# ISEGYE_IDOL.net
KiCad netlist of a schematic drawn in Altium Designer
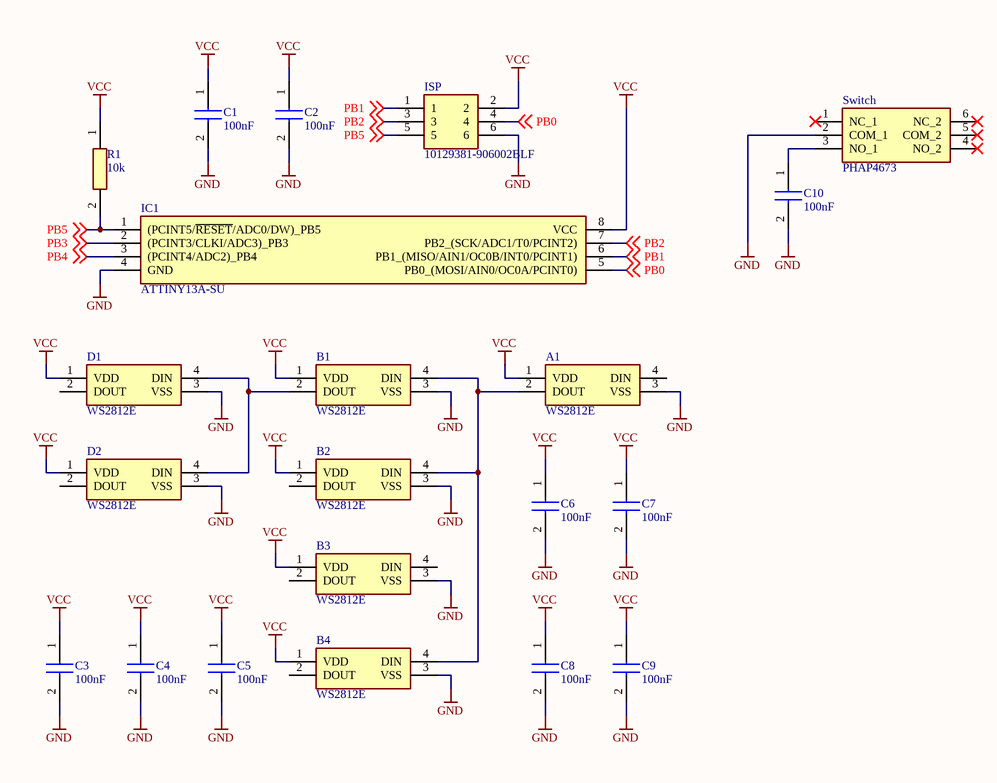
[diagram p0: ISEGYE_IDOL.SchDoc]

(export (version "E")
  (design (tool "Eeschema 10.0.6"))
  (components
    (comp (ref "A1")
      (value "WS2812E")
      (footprint "SamacSys:WS2812E")
      (description "LED")
      (libsource (lib "*") (part "WS2812E"))
    )
    (comp (ref "B1")
      (value "WS2812E")
      (footprint "SamacSys:WS2812E")
      (description "LED")
      (libsource (lib "*") (part "WS2812E"))
    )
    (comp (ref "B2")
      (value "WS2812E")
      (footprint "SamacSys:WS2812E")
      (description "LED")
      (libsource (lib "*") (part "WS2812E"))
    )
    (comp (ref "B3")
      (value "WS2812E")
      (footprint "SamacSys:WS2812E")
      (description "LED")
      (libsource (lib "*") (part "WS2812E"))
    )
    (comp (ref "B4")
      (value "WS2812E")
      (footprint "SamacSys:WS2812E")
      (description "LED")
      (libsource (lib "*") (part "WS2812E"))
    )
    (comp (ref "C1")
      (value "100nF")
      (footprint "SamacSys:CAPC2012X94N")
      (description "Capacitor")
      (fields
        (field (name "MANUFACTURER_PART_NUMBER") "08055A130JAT2A")
        (field (name "MOUSER PART NUMBER") "581-08055A130JAT2A")
      )
      (libsource (lib "*") (part "08055A130JAT2A"))
    )
    (comp (ref "C2")
      (value "100nF")
      (footprint "SamacSys:CAPC2012X94N")
      (description "Capacitor")
      (fields
        (field (name "MANUFACTURER_PART_NUMBER") "08055A130JAT2A")
        (field (name "MOUSER PART NUMBER") "581-08055A130JAT2A")
      )
      (libsource (lib "*") (part "08055A130JAT2A"))
    )
    (comp (ref "C3")
      (value "100nF")
      (footprint "SamacSys:CAPC2012X94N")
      (description "Capacitor")
      (fields
        (field (name "MANUFACTURER_PART_NUMBER") "08055A130JAT2A")
        (field (name "MOUSER PART NUMBER") "581-08055A130JAT2A")
      )
      (libsource (lib "*") (part "08055A130JAT2A"))
    )
    (comp (ref "C4")
      (value "100nF")
      (footprint "SamacSys:CAPC2012X94N")
      (description "Capacitor")
      (fields
        (field (name "MANUFACTURER_PART_NUMBER") "08055A130JAT2A")
        (field (name "MOUSER PART NUMBER") "581-08055A130JAT2A")
      )
      (libsource (lib "*") (part "08055A130JAT2A"))
    )
    (comp (ref "C5")
      (value "100nF")
      (footprint "SamacSys:CAPC2012X94N")
      (description "Capacitor")
      (fields
        (field (name "MANUFACTURER_PART_NUMBER") "08055A130JAT2A")
        (field (name "MOUSER PART NUMBER") "581-08055A130JAT2A")
      )
      (libsource (lib "*") (part "08055A130JAT2A"))
    )
    (comp (ref "C6")
      (value "100nF")
      (footprint "SamacSys:CAPC2012X94N")
      (description "Capacitor")
      (fields
        (field (name "MANUFACTURER_PART_NUMBER") "08055A130JAT2A")
        (field (name "MOUSER PART NUMBER") "581-08055A130JAT2A")
      )
      (libsource (lib "*") (part "08055A130JAT2A"))
    )
    (comp (ref "C7")
      (value "100nF")
      (footprint "SamacSys:CAPC2012X94N")
      (description "Capacitor")
      (fields
        (field (name "MANUFACTURER_PART_NUMBER") "08055A130JAT2A")
        (field (name "MOUSER PART NUMBER") "581-08055A130JAT2A")
      )
      (libsource (lib "*") (part "08055A130JAT2A"))
    )
    (comp (ref "C8")
      (value "100nF")
      (footprint "SamacSys:CAPC2012X94N")
      (description "Capacitor")
      (fields
        (field (name "MANUFACTURER_PART_NUMBER") "08055A130JAT2A")
        (field (name "MOUSER PART NUMBER") "581-08055A130JAT2A")
      )
      (libsource (lib "*") (part "08055A130JAT2A"))
    )
    (comp (ref "C9")
      (value "100nF")
      (footprint "SamacSys:CAPC2012X94N")
      (description "Capacitor")
      (fields
        (field (name "MANUFACTURER_PART_NUMBER") "08055A130JAT2A")
        (field (name "MOUSER PART NUMBER") "581-08055A130JAT2A")
      )
      (libsource (lib "*") (part "08055A130JAT2A"))
    )
    (comp (ref "C10")
      (value "100nF")
      (footprint "SamacSys:CAPC2012X94N")
      (description "Capacitor")
      (fields
        (field (name "MANUFACTURER_PART_NUMBER") "08055A130JAT2A")
        (field (name "MOUSER PART NUMBER") "581-08055A130JAT2A")
      )
      (libsource (lib "*") (part "08055A130JAT2A"))
    )
    (comp (ref "D1")
      (value "WS2812E")
      (footprint "SamacSys:WS2812E")
      (description "LED")
      (libsource (lib "*") (part "WS2812E"))
    )
    (comp (ref "D2")
      (value "WS2812E")
      (footprint "SamacSys:WS2812E")
      (description "LED")
      (libsource (lib "*") (part "WS2812E"))
    )
    (comp (ref "IC1")
      (value "ATTINY13A-SU")
      (footprint "SamacSys:SOIC127P798X216-8N")
      (description "Integrated Circuit")
      (fields (field (name "MOUSER PART NUMBER") "556-ATTINY13A-SU"))
      (libsource (lib "*") (part "ATTINY13A-SU"))
    )
    (comp (ref "ISP")
      (value "10129381-906002BLF")
      (footprint "SamacSys:HDRV6W67P254_2X3_762X483X858P")
      (description "Connector")
      (fields (field (name "MOUSER PART NUMBER") "649-1012938190602BLF"))
      (libsource (lib "*") (part "10129381-906002BLF"))
    )
    (comp (ref "R1")
      (value "10k")
      (footprint "SamacSys:RESC2012X65N")
      (description "Resistor")
      (fields (field (name "MANUFACTURER_PART_NUMBER") "NTR10B1002CTRF"))
      (libsource (lib "*") (part "NTR10B1002CTRF"))
    )
    (comp (ref "Switch")
      (value "PHAP4673")
      (footprint "SamacSys:PHAP4673")
      (description "Switch")
      (fields (field (name "MOUSER PART NUMBER") "642-PHAP4673"))
      (libsource (lib "*") (part "PHAP4673"))
    )
  )
  (nets
    (net (code "1") (name "GND") (class "Default")
      (node (ref "A1") (pin "3") (pinfunction "VSS_3") (pintype "passive"))
      (node (ref "B1") (pin "3") (pinfunction "VSS_3") (pintype "passive"))
      (node (ref "B2") (pin "3") (pinfunction "VSS_3") (pintype "passive"))
      (node (ref "B3") (pin "3") (pinfunction "VSS_3") (pintype "passive"))
      (node (ref "B4") (pin "3") (pinfunction "VSS_3") (pintype "passive"))
      (node (ref "C1") (pin "2") (pinfunction "2_2") (pintype "passive"))
      (node (ref "C10") (pin "2") (pinfunction "2_2") (pintype "passive"))
      (node (ref "C2") (pin "2") (pinfunction "2_2") (pintype "passive"))
      (node (ref "C3") (pin "2") (pinfunction "2_2") (pintype "passive"))
      (node (ref "C4") (pin "2") (pinfunction "2_2") (pintype "passive"))
      (node (ref "C5") (pin "2") (pinfunction "2_2") (pintype "passive"))
      (node (ref "C6") (pin "2") (pinfunction "2_2") (pintype "passive"))
      (node (ref "C7") (pin "2") (pinfunction "2_2") (pintype "passive"))
      (node (ref "C8") (pin "2") (pinfunction "2_2") (pintype "passive"))
      (node (ref "C9") (pin "2") (pinfunction "2_2") (pintype "passive"))
      (node (ref "D1") (pin "3") (pinfunction "VSS_3") (pintype "passive"))
      (node (ref "D2") (pin "3") (pinfunction "VSS_3") (pintype "passive"))
      (node (ref "IC1") (pin "4") (pinfunction "GND_4") (pintype "passive"))
      (node (ref "ISP") (pin "6") (pinfunction "6_6") (pintype "passive"))
      (node (ref "Switch") (pin "2") (pinfunction "COM_1_2") (pintype "passive"))
    )
    (net (code "2") (name "Net-(A1-DOUT)") (class "Default")
      (node (ref "A1") (pin "2") (pinfunction "DOUT_2") (pintype "passive"))
      (node (ref "B1") (pin "4") (pinfunction "DIN_4") (pintype "passive"))
      (node (ref "B2") (pin "4") (pinfunction "DIN_4") (pintype "passive"))
      (node (ref "B4") (pin "4") (pinfunction "DIN_4") (pintype "passive"))
    )
    (net (code "3") (name "Net-(B1-DOUT)") (class "Default")
      (node (ref "B1") (pin "2") (pinfunction "DOUT_2") (pintype "passive"))
      (node (ref "D1") (pin "4") (pinfunction "DIN_4") (pintype "passive"))
      (node (ref "D2") (pin "4") (pinfunction "DIN_4") (pintype "passive"))
    )
    (net (code "4") (name "Net-(Switch-NO_1)") (class "Default")
      (node (ref "C10") (pin "1") (pinfunction "1_1") (pintype "passive"))
      (node (ref "Switch") (pin "3") (pinfunction "NO_1_3") (pintype "passive"))
    )
    (net (code "5") (name "PB0") (class "Default")
      (node (ref "IC1") (pin "5") (pinfunction "PB0_(MOSI/AIN0/OC0A/PCINT0)_5") (pintype "passive"))
      (node (ref "ISP") (pin "4") (pinfunction "4_4") (pintype "passive"))
    )
    (net (code "6") (name "PB1") (class "Default")
      (node (ref "IC1") (pin "6") (pinfunction "PB1_(MISO/AIN1/OC0B/INT0/PCINT1)_6") (pintype "passive"))
      (node (ref "ISP") (pin "1") (pinfunction "1_1") (pintype "passive"))
    )
    (net (code "7") (name "PB2") (class "Default")
      (node (ref "IC1") (pin "7") (pinfunction "PB2_(SCK/ADC1/T0/PCINT2)_7") (pintype "passive"))
      (node (ref "ISP") (pin "3") (pinfunction "3_3") (pintype "passive"))
    )
    (net (code "8") (name "PB3") (class "Default")
      (node (ref "IC1") (pin "2") (pinfunction "(PCINT3/CLKI/ADC3)_PB3_2") (pintype "passive"))
    )
    (net (code "9") (name "PB4") (class "Default")
      (node (ref "IC1") (pin "3") (pinfunction "(PCINT4/ADC2)_PB4_3") (pintype "passive"))
    )
    (net (code "10") (name "PB5") (class "Default")
      (node (ref "IC1") (pin "1") (pinfunction "(PCINT5/~{RESET}/ADC0/DW)_PB5_1") (pintype "passive"))
      (node (ref "ISP") (pin "5") (pinfunction "5_5") (pintype "passive"))
      (node (ref "R1") (pin "2") (pinfunction "2_2") (pintype "passive"))
    )
    (net (code "11") (name "VCC") (class "Default")
      (node (ref "A1") (pin "1") (pinfunction "VDD_1") (pintype "passive"))
      (node (ref "B1") (pin "1") (pinfunction "VDD_1") (pintype "passive"))
      (node (ref "B2") (pin "1") (pinfunction "VDD_1") (pintype "passive"))
      (node (ref "B3") (pin "1") (pinfunction "VDD_1") (pintype "passive"))
      (node (ref "B4") (pin "1") (pinfunction "VDD_1") (pintype "passive"))
      (node (ref "C1") (pin "1") (pinfunction "1_1") (pintype "passive"))
      (node (ref "C2") (pin "1") (pinfunction "1_1") (pintype "passive"))
      (node (ref "C3") (pin "1") (pinfunction "1_1") (pintype "passive"))
      (node (ref "C4") (pin "1") (pinfunction "1_1") (pintype "passive"))
      (node (ref "C5") (pin "1") (pinfunction "1_1") (pintype "passive"))
      (node (ref "C6") (pin "1") (pinfunction "1_1") (pintype "passive"))
      (node (ref "C7") (pin "1") (pinfunction "1_1") (pintype "passive"))
      (node (ref "C8") (pin "1") (pinfunction "1_1") (pintype "passive"))
      (node (ref "C9") (pin "1") (pinfunction "1_1") (pintype "passive"))
      (node (ref "D1") (pin "1") (pinfunction "VDD_1") (pintype "passive"))
      (node (ref "D2") (pin "1") (pinfunction "VDD_1") (pintype "passive"))
      (node (ref "IC1") (pin "8") (pinfunction "VCC_8") (pintype "passive"))
      (node (ref "ISP") (pin "2") (pinfunction "2_2") (pintype "passive"))
      (node (ref "R1") (pin "1") (pinfunction "1_1") (pintype "passive"))
    )
    (net (code "12") (name "unconnected-(A1-DIN-Pad4)") (class "Default")
      (node (ref "A1") (pin "4") (pinfunction "DIN_4") (pintype "passive"))
    )
    (net (code "13") (name "unconnected-(B2-DOUT-Pad2)") (class "Default")
      (node (ref "B2") (pin "2") (pinfunction "DOUT_2") (pintype "passive"))
    )
    (net (code "14") (name "unconnected-(B3-DIN-Pad4)") (class "Default")
      (node (ref "B3") (pin "4") (pinfunction "DIN_4") (pintype "passive"))
    )
    (net (code "15") (name "unconnected-(B3-DOUT-Pad2)") (class "Default")
      (node (ref "B3") (pin "2") (pinfunction "DOUT_2") (pintype "passive"))
    )
    (net (code "16") (name "unconnected-(B4-DOUT-Pad2)") (class "Default")
      (node (ref "B4") (pin "2") (pinfunction "DOUT_2") (pintype "passive"))
    )
    (net (code "17") (name "unconnected-(D1-DOUT-Pad2)") (class "Default")
      (node (ref "D1") (pin "2") (pinfunction "DOUT_2") (pintype "passive"))
    )
    (net (code "18") (name "unconnected-(D2-DOUT-Pad2)") (class "Default")
      (node (ref "D2") (pin "2") (pinfunction "DOUT_2") (pintype "passive"))
    )
    (net (code "19") (name "unconnected-(Switch-COM_2-Pad5)") (class "Default")
      (node (ref "Switch") (pin "5") (pinfunction "COM_2_5") (pintype "passive+no_connect"))
    )
    (net (code "20") (name "unconnected-(Switch-NC_1-Pad1)") (class "Default")
      (node (ref "Switch") (pin "1") (pinfunction "NC_1_1") (pintype "passive+no_connect"))
    )
    (net (code "21") (name "unconnected-(Switch-NC_2-Pad6)") (class "Default")
      (node (ref "Switch") (pin "6") (pinfunction "NC_2_6") (pintype "passive+no_connect"))
    )
    (net (code "22") (name "unconnected-(Switch-NO_2-Pad4)") (class "Default")
      (node (ref "Switch") (pin "4") (pinfunction "NO_2_4") (pintype "passive+no_connect"))
    )
  )
)
